# LIC_rack_TS_ext-00.net
KiCad netlist of a schematic drawn in EAGLE
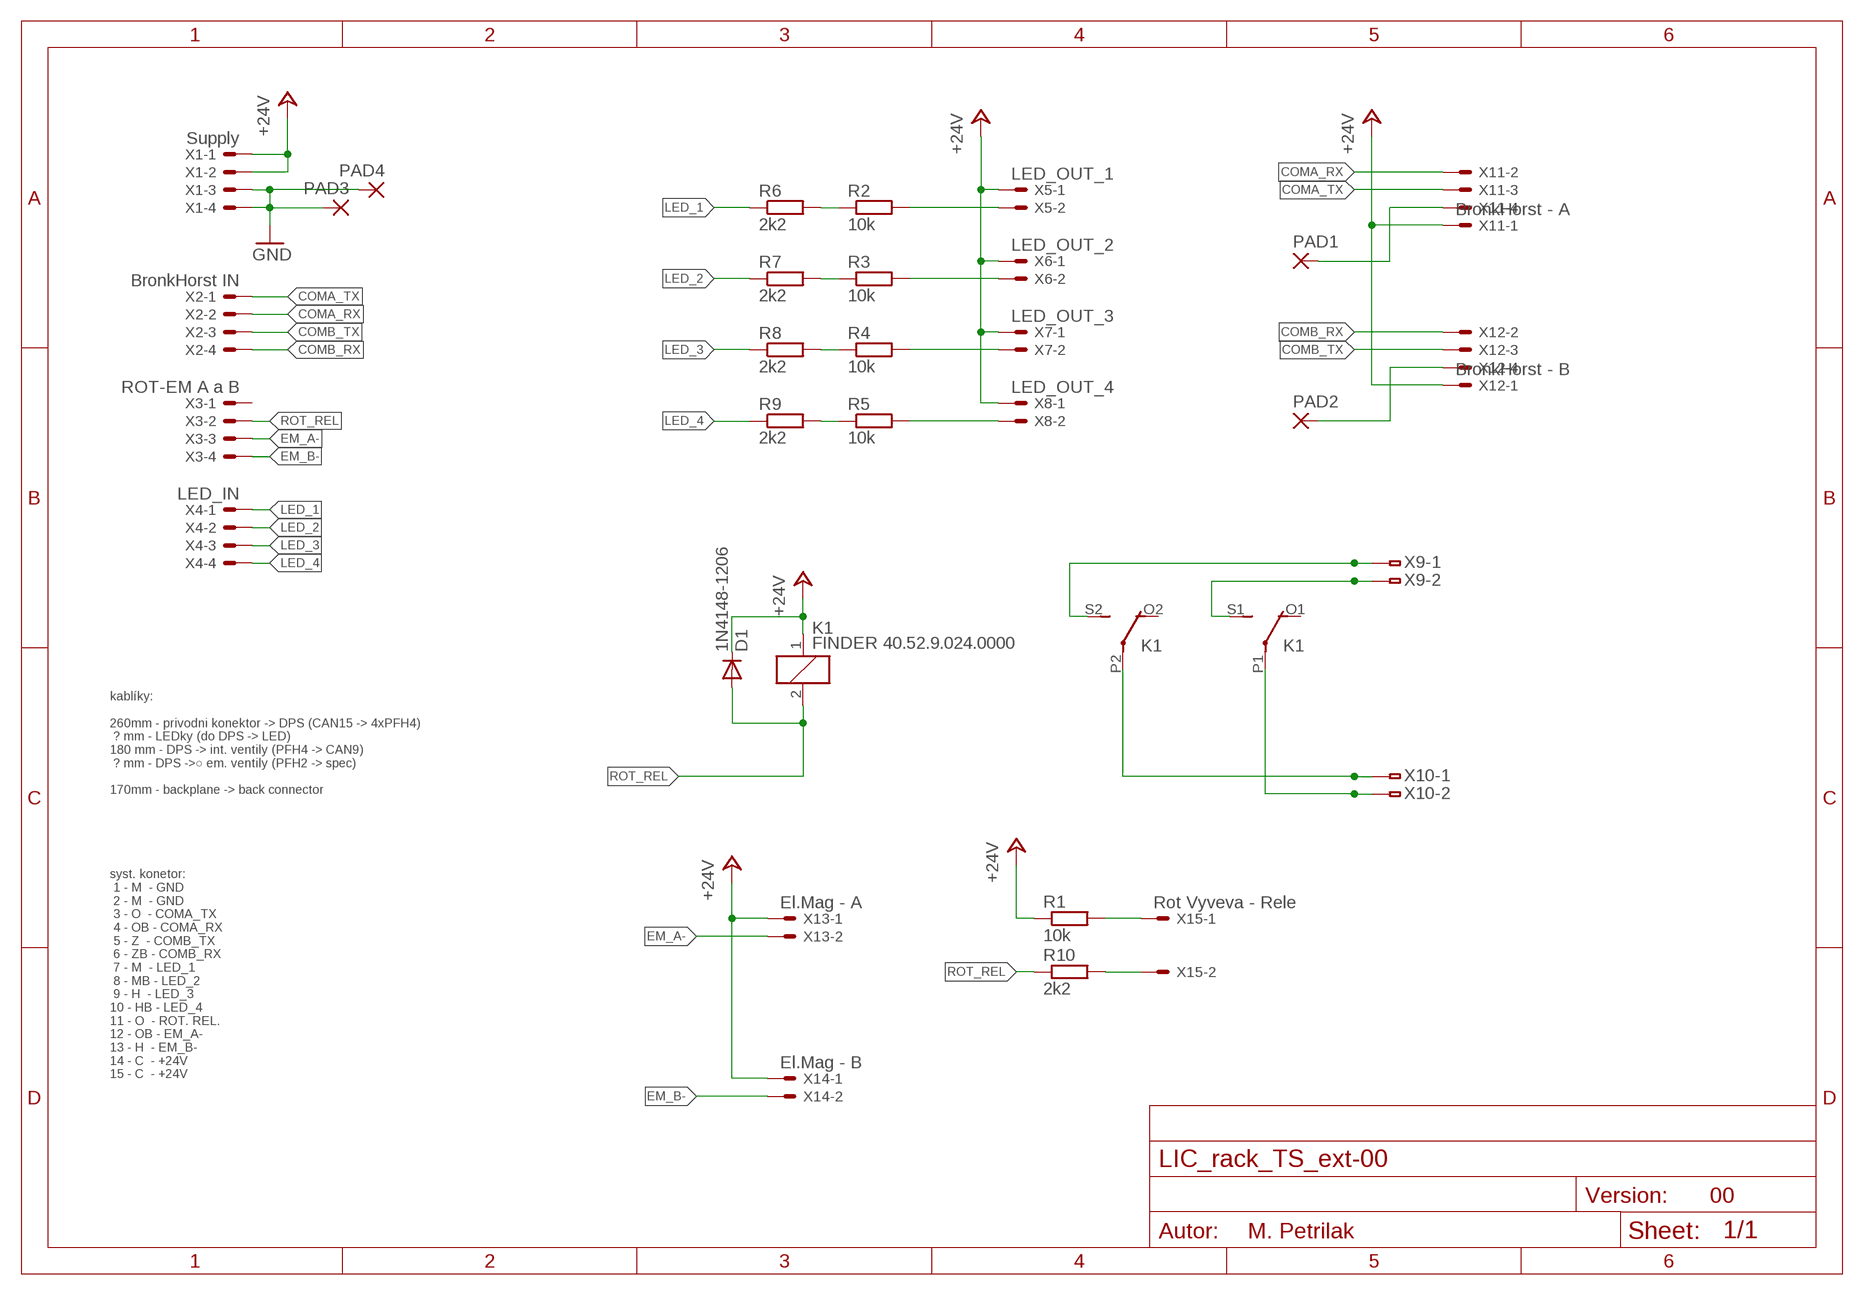
[diagram p0: schematic, sheet 1]

(export (version "E")
  (design (tool "Eeschema 10.0.6"))
  (components
    (comp (ref "D1")
      (value "1N4148-1206")
      (footprint "eagle-import:R1206")
      (libsource (lib "eagle-import") (part "1N4148-1206"))
    )
    (comp (ref "K1")
      (value "FINDER 40.52.9.024.0000")
      (footprint "eagle-import:F4052")
      (libsource (lib "eagle-import") (part "4052"))
    )
    (comp (ref "PAD1")
      (value "SMD-2X3")
      (footprint "eagle-import:SMD2-3")
      (libsource (lib "eagle-import") (part "SMD-2X3"))
    )
    (comp (ref "PAD2")
      (value "SMD-2X3")
      (footprint "eagle-import:SMD2-3")
      (libsource (lib "eagle-import") (part "SMD-2X3"))
    )
    (comp (ref "PAD3")
      (value "SMD-2X3")
      (footprint "eagle-import:SMD2-3")
      (libsource (lib "eagle-import") (part "SMD-2X3"))
    )
    (comp (ref "PAD4")
      (value "SMD-2X3")
      (footprint "eagle-import:SMD2-3")
      (libsource (lib "eagle-import") (part "SMD-2X3"))
    )
    (comp (ref "R1")
      (value "10k")
      (footprint "eagle-import:R1206")
      (libsource (lib "eagle-import") (part "R-EU_R1206"))
    )
    (comp (ref "R2")
      (value "10k")
      (footprint "eagle-import:R1206")
      (libsource (lib "eagle-import") (part "R-EU_R1206"))
    )
    (comp (ref "R3")
      (value "10k")
      (footprint "eagle-import:R1206")
      (libsource (lib "eagle-import") (part "R-EU_R1206"))
    )
    (comp (ref "R4")
      (value "10k")
      (footprint "eagle-import:R1206")
      (libsource (lib "eagle-import") (part "R-EU_R1206"))
    )
    (comp (ref "R5")
      (value "10k")
      (footprint "eagle-import:R1206")
      (libsource (lib "eagle-import") (part "R-EU_R1206"))
    )
    (comp (ref "R6")
      (value "2k2")
      (footprint "eagle-import:R1206")
      (libsource (lib "eagle-import") (part "R-EU_R1206"))
    )
    (comp (ref "R7")
      (value "2k2")
      (footprint "eagle-import:R1206")
      (libsource (lib "eagle-import") (part "R-EU_R1206"))
    )
    (comp (ref "R8")
      (value "2k2")
      (footprint "eagle-import:R1206")
      (libsource (lib "eagle-import") (part "R-EU_R1206"))
    )
    (comp (ref "R9")
      (value "2k2")
      (footprint "eagle-import:R1206")
      (libsource (lib "eagle-import") (part "R-EU_R1206"))
    )
    (comp (ref "R10")
      (value "2k2")
      (footprint "eagle-import:R1206")
      (libsource (lib "eagle-import") (part "R-EU_R1206"))
    )
    (comp (ref "X1")
      (value "Supply")
      (footprint "eagle-import:22-23-2041")
      (libsource (lib "eagle-import") (part "22-23-2041"))
    )
    (comp (ref "X2")
      (value "BronkHorst IN")
      (footprint "eagle-import:22-23-2041")
      (libsource (lib "eagle-import") (part "22-23-2041"))
    )
    (comp (ref "X3")
      (value "ROT-EM A a B")
      (footprint "eagle-import:22-23-2041")
      (libsource (lib "eagle-import") (part "22-23-2041"))
    )
    (comp (ref "X4")
      (value "LED_IN")
      (footprint "eagle-import:22-23-2041")
      (libsource (lib "eagle-import") (part "22-23-2041"))
    )
    (comp (ref "X5")
      (value "LED_OUT_1")
      (footprint "eagle-import:22-23-2021")
      (libsource (lib "eagle-import") (part "22-23-2021"))
    )
    (comp (ref "X6")
      (value "LED_OUT_2")
      (footprint "eagle-import:22-23-2021")
      (libsource (lib "eagle-import") (part "22-23-2021"))
    )
    (comp (ref "X7")
      (value "LED_OUT_3")
      (footprint "eagle-import:22-23-2021")
      (libsource (lib "eagle-import") (part "22-23-2021"))
    )
    (comp (ref "X8")
      (value "LED_OUT_4")
      (footprint "eagle-import:22-23-2021")
      (libsource (lib "eagle-import") (part "22-23-2021"))
    )
    (comp (ref "X9")
      (value "High Voltage Supply - L")
      (footprint "eagle-import:WAGO236-401_2")
      (libsource (lib "eagle-import") (part "WAGO236-401/2"))
    )
    (comp (ref "X10")
      (value "High Voltage Supply - N")
      (footprint "eagle-import:WAGO236-401_2")
      (libsource (lib "eagle-import") (part "WAGO236-401/2"))
    )
    (comp (ref "X11")
      (value "BronkHorst - A")
      (footprint "eagle-import:22-23-2041")
      (libsource (lib "eagle-import") (part "22-23-2041"))
    )
    (comp (ref "X12")
      (value "BronkHorst - B")
      (footprint "eagle-import:22-23-2041")
      (libsource (lib "eagle-import") (part "22-23-2041"))
    )
    (comp (ref "X13")
      (value "El.Mag - A")
      (footprint "eagle-import:22-23-2021")
      (libsource (lib "eagle-import") (part "22-23-2021"))
    )
    (comp (ref "X14")
      (value "El.Mag - B")
      (footprint "eagle-import:22-23-2021")
      (libsource (lib "eagle-import") (part "22-23-2021"))
    )
    (comp (ref "X15")
      (value "Rot Vyveva - Rele")
      (footprint "eagle-import:22-23-2021")
      (libsource (lib "eagle-import") (part "22-23-2021"))
    )
  )
  (nets
    (net (code "1") (name "+24V") (class "Default")
      (node (ref "D1") (pin "K") (pinfunction "C_K") (pintype "passive"))
      (node (ref "K1") (pin "1") (pinfunction "1_1") (pintype "passive"))
      (node (ref "R1") (pin "1") (pinfunction "1_1") (pintype "passive"))
      (node (ref "X1") (pin "1") (pinfunction "S_1") (pintype "passive"))
      (node (ref "X1") (pin "2") (pinfunction "S_2") (pintype "passive"))
      (node (ref "X11") (pin "1") (pinfunction "S_1") (pintype "passive"))
      (node (ref "X12") (pin "1") (pinfunction "S_1") (pintype "passive"))
      (node (ref "X13") (pin "1") (pinfunction "S_1") (pintype "passive"))
      (node (ref "X14") (pin "1") (pinfunction "S_1") (pintype "passive"))
      (node (ref "X5") (pin "1") (pinfunction "S_1") (pintype "passive"))
      (node (ref "X6") (pin "1") (pinfunction "S_1") (pintype "passive"))
      (node (ref "X7") (pin "1") (pinfunction "S_1") (pintype "passive"))
      (node (ref "X8") (pin "1") (pinfunction "S_1") (pintype "passive"))
    )
    (net (code "2") (name "COMA_RX") (class "Default")
      (node (ref "X11") (pin "2") (pinfunction "S_2") (pintype "passive"))
      (node (ref "X2") (pin "2") (pinfunction "S_2") (pintype "passive"))
    )
    (net (code "3") (name "COMA_TX") (class "Default")
      (node (ref "X11") (pin "3") (pinfunction "S_3") (pintype "passive"))
      (node (ref "X2") (pin "1") (pinfunction "S_1") (pintype "passive"))
    )
    (net (code "4") (name "COMB_RX") (class "Default")
      (node (ref "X12") (pin "2") (pinfunction "S_2") (pintype "passive"))
      (node (ref "X2") (pin "4") (pinfunction "S_4") (pintype "passive"))
    )
    (net (code "5") (name "COMB_TX") (class "Default")
      (node (ref "X12") (pin "3") (pinfunction "S_3") (pintype "passive"))
      (node (ref "X2") (pin "3") (pinfunction "S_3") (pintype "passive"))
    )
    (net (code "6") (name "EM_A-") (class "Default")
      (node (ref "X13") (pin "2") (pinfunction "S_2") (pintype "passive"))
      (node (ref "X3") (pin "3") (pinfunction "S_3") (pintype "passive"))
    )
    (net (code "7") (name "EM_B-") (class "Default")
      (node (ref "X14") (pin "2") (pinfunction "S_2") (pintype "passive"))
      (node (ref "X3") (pin "4") (pinfunction "S_4") (pintype "passive"))
    )
    (net (code "8") (name "GND") (class "Default")
      (node (ref "PAD3") (pin "1") (pinfunction "P_1") (pintype "passive"))
      (node (ref "PAD4") (pin "1") (pinfunction "P_1") (pintype "passive"))
      (node (ref "X1") (pin "3") (pinfunction "S_3") (pintype "passive"))
      (node (ref "X1") (pin "4") (pinfunction "S_4") (pintype "passive"))
    )
    (net (code "9") (name "LED_1") (class "Default")
      (node (ref "R6") (pin "1") (pinfunction "1_1") (pintype "passive"))
      (node (ref "X4") (pin "1") (pinfunction "S_1") (pintype "passive"))
    )
    (net (code "10") (name "LED_2") (class "Default")
      (node (ref "R7") (pin "1") (pinfunction "1_1") (pintype "passive"))
      (node (ref "X4") (pin "2") (pinfunction "S_2") (pintype "passive"))
    )
    (net (code "11") (name "LED_3") (class "Default")
      (node (ref "R8") (pin "1") (pinfunction "1_1") (pintype "passive"))
      (node (ref "X4") (pin "3") (pinfunction "S_3") (pintype "passive"))
    )
    (net (code "12") (name "LED_4") (class "Default")
      (node (ref "R9") (pin "1") (pinfunction "1_1") (pintype "passive"))
      (node (ref "X4") (pin "4") (pinfunction "S_4") (pintype "passive"))
    )
    (net (code "13") (name "Net-(K1B-P)") (class "Default")
      (node (ref "K1") (pin "P1") (pinfunction "P_P1") (pintype "passive"))
      (node (ref "X10") (pin "2A") (pinfunction "1_2A") (pintype "passive"))
      (node (ref "X10") (pin "2B") (pinfunction "2_2B") (pintype "passive"))
    )
    (net (code "14") (name "Net-(K1B-S)") (class "Default")
      (node (ref "K1") (pin "S1") (pinfunction "S_S1") (pintype "passive"))
      (node (ref "X9") (pin "2A") (pinfunction "1_2A") (pintype "passive"))
      (node (ref "X9") (pin "2B") (pinfunction "2_2B") (pintype "passive"))
    )
    (net (code "15") (name "Net-(K1C-P)") (class "Default")
      (node (ref "K1") (pin "P2") (pinfunction "P_P2") (pintype "passive"))
      (node (ref "X10") (pin "1A") (pinfunction "1_1A") (pintype "passive"))
      (node (ref "X10") (pin "1B") (pinfunction "2_1B") (pintype "passive"))
    )
    (net (code "16") (name "Net-(K1C-S)") (class "Default")
      (node (ref "K1") (pin "S2") (pinfunction "S_S2") (pintype "passive"))
      (node (ref "X9") (pin "1A") (pinfunction "1_1A") (pintype "passive"))
      (node (ref "X9") (pin "1B") (pinfunction "2_1B") (pintype "passive"))
    )
    (net (code "17") (name "Net-(PAD1-P)") (class "Default")
      (node (ref "PAD1") (pin "1") (pinfunction "P_1") (pintype "passive"))
      (node (ref "X11") (pin "4") (pinfunction "S_4") (pintype "passive"))
    )
    (net (code "18") (name "Net-(PAD2-P)") (class "Default")
      (node (ref "PAD2") (pin "1") (pinfunction "P_1") (pintype "passive"))
      (node (ref "X12") (pin "4") (pinfunction "S_4") (pintype "passive"))
    )
    (net (code "19") (name "Net-(R2-Pad1)") (class "Default")
      (node (ref "R2") (pin "1") (pinfunction "1_1") (pintype "passive"))
      (node (ref "R6") (pin "2") (pinfunction "2_2") (pintype "passive"))
    )
    (net (code "20") (name "Net-(R3-Pad1)") (class "Default")
      (node (ref "R3") (pin "1") (pinfunction "1_1") (pintype "passive"))
      (node (ref "R7") (pin "2") (pinfunction "2_2") (pintype "passive"))
    )
    (net (code "21") (name "Net-(R4-Pad1)") (class "Default")
      (node (ref "R4") (pin "1") (pinfunction "1_1") (pintype "passive"))
      (node (ref "R8") (pin "2") (pinfunction "2_2") (pintype "passive"))
    )
    (net (code "22") (name "Net-(R5-Pad1)") (class "Default")
      (node (ref "R5") (pin "1") (pinfunction "1_1") (pintype "passive"))
      (node (ref "R9") (pin "2") (pinfunction "2_2") (pintype "passive"))
    )
    (net (code "23") (name "Net-(X5B-S)") (class "Default")
      (node (ref "R2") (pin "2") (pinfunction "2_2") (pintype "passive"))
      (node (ref "X5") (pin "2") (pinfunction "S_2") (pintype "passive"))
    )
    (net (code "24") (name "Net-(X6B-S)") (class "Default")
      (node (ref "R3") (pin "2") (pinfunction "2_2") (pintype "passive"))
      (node (ref "X6") (pin "2") (pinfunction "S_2") (pintype "passive"))
    )
    (net (code "25") (name "Net-(X7B-S)") (class "Default")
      (node (ref "R4") (pin "2") (pinfunction "2_2") (pintype "passive"))
      (node (ref "X7") (pin "2") (pinfunction "S_2") (pintype "passive"))
    )
    (net (code "26") (name "Net-(X8B-S)") (class "Default")
      (node (ref "R5") (pin "2") (pinfunction "2_2") (pintype "passive"))
      (node (ref "X8") (pin "2") (pinfunction "S_2") (pintype "passive"))
    )
    (net (code "27") (name "Net-(X15A-S)") (class "Default")
      (node (ref "R1") (pin "2") (pinfunction "2_2") (pintype "passive"))
      (node (ref "X15") (pin "1") (pinfunction "S_1") (pintype "passive"))
    )
    (net (code "28") (name "Net-(X15B-S)") (class "Default")
      (node (ref "R10") (pin "2") (pinfunction "2_2") (pintype "passive"))
      (node (ref "X15") (pin "2") (pinfunction "S_2") (pintype "passive"))
    )
    (net (code "29") (name "ROT_REL") (class "Default")
      (node (ref "D1") (pin "A") (pinfunction "A_A") (pintype "passive"))
      (node (ref "K1") (pin "2") (pinfunction "2_2") (pintype "passive"))
      (node (ref "R10") (pin "1") (pinfunction "1_1") (pintype "passive"))
      (node (ref "X3") (pin "2") (pinfunction "S_2") (pintype "passive"))
    )
    (net (code "30") (name "unconnected-(K1B-O-PadO1)") (class "Default")
      (node (ref "K1") (pin "O1") (pinfunction "O_O1") (pintype "passive"))
    )
    (net (code "31") (name "unconnected-(K1C-O-PadO2)") (class "Default")
      (node (ref "K1") (pin "O2") (pinfunction "O_O2") (pintype "passive"))
    )
    (net (code "32") (name "unconnected-(X3A-S-Pad1)") (class "Default")
      (node (ref "X3") (pin "1") (pinfunction "S_1") (pintype "passive"))
    )
  )
)
